# IDC_EXT_Connectors.net
KiCad netlist of a schematic drawn in Altium Designer
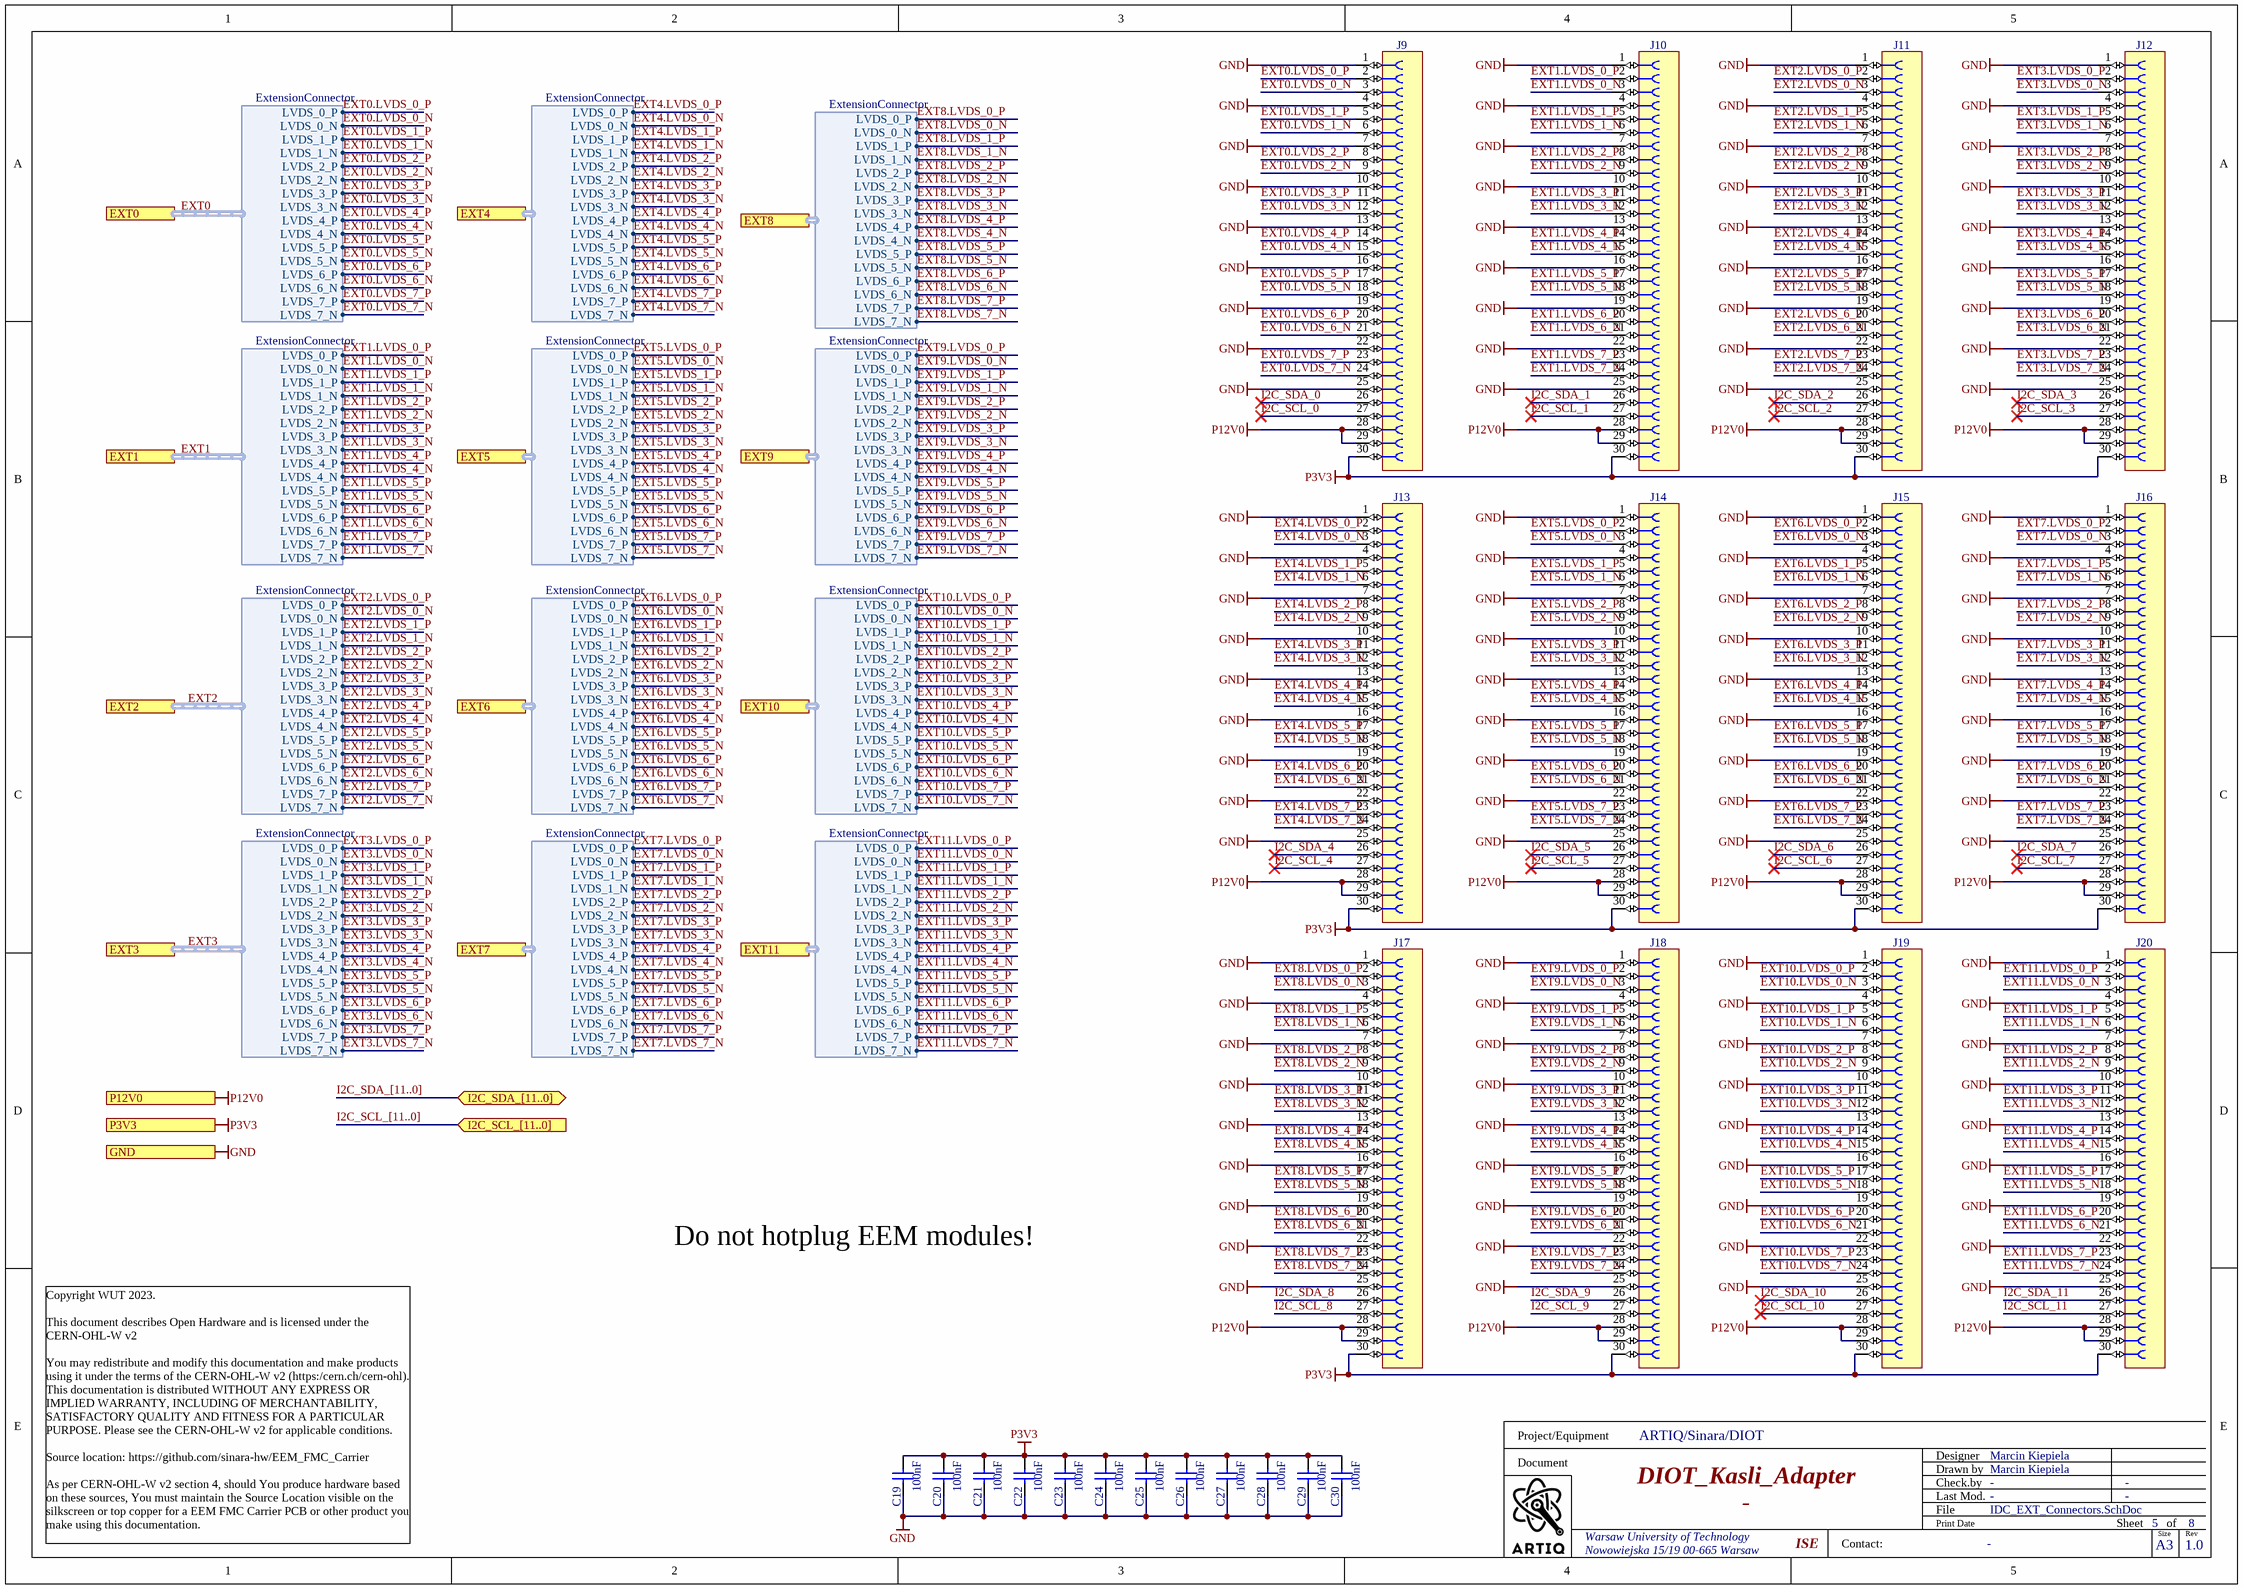
[diagram p0: IDC_EXT_Connectors.SchDoc]

(export (version "E")
  (design (tool "Eeschema 10.0.6"))
  (components
    (comp (ref "C19")
      (value "100nF")
      (footprint "CAPC0603X33N")
      (description "Non-polarised capacitor")
      (fields (field (name "PART NUMBER") "CC0201_100NF_6.3V_10%_X5R") (field (name "VOLTAGE") "6.3V"))
      (libsource (lib "Capacitors") (part "Capacitor - non polarized"))
    )
    (comp (ref "C20")
      (value "100nF")
      (footprint "CAPC0603X33N")
      (description "Non-polarised capacitor")
      (fields (field (name "PART NUMBER") "CC0201_100NF_6.3V_10%_X5R") (field (name "VOLTAGE") "6.3V"))
      (libsource (lib "Capacitors") (part "Capacitor - non polarized"))
    )
    (comp (ref "C21")
      (value "100nF")
      (footprint "CAPC0603X33N")
      (description "Non-polarised capacitor")
      (fields (field (name "PART NUMBER") "CC0201_100NF_6.3V_10%_X5R") (field (name "VOLTAGE") "6.3V"))
      (libsource (lib "Capacitors") (part "Capacitor - non polarized"))
    )
    (comp (ref "C22")
      (value "100nF")
      (footprint "CAPC0603X33N")
      (description "Non-polarised capacitor")
      (fields (field (name "PART NUMBER") "CC0201_100NF_6.3V_10%_X5R") (field (name "VOLTAGE") "6.3V"))
      (libsource (lib "Capacitors") (part "Capacitor - non polarized"))
    )
    (comp (ref "C23")
      (value "100nF")
      (footprint "CAPC0603X33N")
      (description "Non-polarised capacitor")
      (fields (field (name "PART NUMBER") "CC0201_100NF_6.3V_10%_X5R") (field (name "VOLTAGE") "6.3V"))
      (libsource (lib "Capacitors") (part "Capacitor - non polarized"))
    )
    (comp (ref "C24")
      (value "100nF")
      (footprint "CAPC0603X33N")
      (description "Non-polarised capacitor")
      (fields (field (name "PART NUMBER") "CC0201_100NF_6.3V_10%_X5R") (field (name "VOLTAGE") "6.3V"))
      (libsource (lib "Capacitors") (part "Capacitor - non polarized"))
    )
    (comp (ref "C25")
      (value "100nF")
      (footprint "CAPC0603X33N")
      (description "Non-polarised capacitor")
      (fields (field (name "PART NUMBER") "CC0201_100NF_6.3V_10%_X5R") (field (name "VOLTAGE") "6.3V"))
      (libsource (lib "Capacitors") (part "Capacitor - non polarized"))
    )
    (comp (ref "C26")
      (value "100nF")
      (footprint "CAPC0603X33N")
      (description "Non-polarised capacitor")
      (fields (field (name "PART NUMBER") "CC0201_100NF_6.3V_10%_X5R") (field (name "VOLTAGE") "6.3V"))
      (libsource (lib "Capacitors") (part "Capacitor - non polarized"))
    )
    (comp (ref "C27")
      (value "100nF")
      (footprint "CAPC0603X33N")
      (description "Non-polarised capacitor")
      (fields (field (name "PART NUMBER") "CC0201_100NF_6.3V_10%_X5R") (field (name "VOLTAGE") "6.3V"))
      (libsource (lib "Capacitors") (part "Capacitor - non polarized"))
    )
    (comp (ref "C28")
      (value "100nF")
      (footprint "CAPC0603X33N")
      (description "Non-polarised capacitor")
      (fields (field (name "PART NUMBER") "CC0201_100NF_6.3V_10%_X5R") (field (name "VOLTAGE") "6.3V"))
      (libsource (lib "Capacitors") (part "Capacitor - non polarized"))
    )
    (comp (ref "C29")
      (value "100nF")
      (footprint "CAPC0603X33N")
      (description "Non-polarised capacitor")
      (fields (field (name "PART NUMBER") "CC0201_100NF_6.3V_10%_X5R") (field (name "VOLTAGE") "6.3V"))
      (libsource (lib "Capacitors") (part "Capacitor - non polarized"))
    )
    (comp (ref "C30")
      (value "100nF")
      (footprint "CAPC0603X33N")
      (description "Non-polarised capacitor")
      (fields (field (name "PART NUMBER") "CC0201_100NF_6.3V_10%_X5R") (field (name "VOLTAGE") "6.3V"))
      (libsource (lib "Capacitors") (part "Capacitor - non polarized"))
    )
    (comp (ref "J9")
      (value "~")
      (footprint "SAMTEC_ESW-115-44-L-D")
      (description "Elevated Socket Strip, 0.100\" Pitch (2.54mm) Through Hole Gold, 30 pos, duble row")
      (fields (field (name "PART NUMBER") "ESW-115-44-L-D") (field (name "MANUFACTURER") "Samtec"))
      (libsource (lib "MKI_library") (part "CernLib Connector 30 Female"))
    )
    (comp (ref "J10")
      (value "~")
      (footprint "SAMTEC_ESW-115-44-L-D")
      (description "Elevated Socket Strip, 0.100\" Pitch (2.54mm) Through Hole Gold, 30 pos, duble row")
      (fields (field (name "PART NUMBER") "ESW-115-44-L-D") (field (name "MANUFACTURER") "Samtec"))
      (libsource (lib "MKI_library") (part "CernLib Connector 30 Female"))
    )
    (comp (ref "J11")
      (value "~")
      (footprint "SAMTEC_ESW-115-44-L-D")
      (description "Elevated Socket Strip, 0.100\" Pitch (2.54mm) Through Hole Gold, 30 pos, duble row")
      (fields (field (name "PART NUMBER") "ESW-115-44-L-D") (field (name "MANUFACTURER") "Samtec"))
      (libsource (lib "MKI_library") (part "CernLib Connector 30 Female"))
    )
    (comp (ref "J12")
      (value "~")
      (footprint "SAMTEC_ESW-115-44-L-D")
      (description "Elevated Socket Strip, 0.100\" Pitch (2.54mm) Through Hole Gold, 30 pos, duble row")
      (fields (field (name "PART NUMBER") "ESW-115-44-L-D") (field (name "MANUFACTURER") "Samtec"))
      (libsource (lib "MKI_library") (part "CernLib Connector 30 Female"))
    )
    (comp (ref "J13")
      (value "~")
      (footprint "SAMTEC_ESW-115-44-L-D")
      (description "Elevated Socket Strip, 0.100\" Pitch (2.54mm) Through Hole Gold, 30 pos, duble row")
      (fields (field (name "PART NUMBER") "ESW-115-44-L-D") (field (name "MANUFACTURER") "Samtec"))
      (libsource (lib "MKI_library") (part "CernLib Connector 30 Female"))
    )
    (comp (ref "J14")
      (value "~")
      (footprint "SAMTEC_ESW-115-44-L-D")
      (description "Elevated Socket Strip, 0.100\" Pitch (2.54mm) Through Hole Gold, 30 pos, duble row")
      (fields (field (name "PART NUMBER") "ESW-115-44-L-D") (field (name "MANUFACTURER") "Samtec"))
      (libsource (lib "MKI_library") (part "CernLib Connector 30 Female"))
    )
    (comp (ref "J15")
      (value "~")
      (footprint "SAMTEC_ESW-115-44-L-D")
      (description "Elevated Socket Strip, 0.100\" Pitch (2.54mm) Through Hole Gold, 30 pos, duble row")
      (fields (field (name "PART NUMBER") "ESW-115-44-L-D") (field (name "MANUFACTURER") "Samtec"))
      (libsource (lib "MKI_library") (part "CernLib Connector 30 Female"))
    )
    (comp (ref "J16")
      (value "~")
      (footprint "SAMTEC_ESW-115-44-L-D")
      (description "Elevated Socket Strip, 0.100\" Pitch (2.54mm) Through Hole Gold, 30 pos, duble row")
      (fields (field (name "PART NUMBER") "ESW-115-44-L-D") (field (name "MANUFACTURER") "Samtec"))
      (libsource (lib "MKI_library") (part "CernLib Connector 30 Female"))
    )
    (comp (ref "J17")
      (value "~")
      (footprint "SAMTEC_ESW-115-44-L-D")
      (description "Elevated Socket Strip, 0.100\" Pitch (2.54mm) Through Hole Gold, 30 pos, duble row")
      (fields (field (name "PART NUMBER") "ESW-115-44-L-D") (field (name "MANUFACTURER") "Samtec"))
      (libsource (lib "MKI_library") (part "CernLib Connector 30 Female"))
    )
    (comp (ref "J18")
      (value "~")
      (footprint "SAMTEC_ESW-115-44-L-D")
      (description "Elevated Socket Strip, 0.100\" Pitch (2.54mm) Through Hole Gold, 30 pos, duble row")
      (fields (field (name "PART NUMBER") "ESW-115-44-L-D") (field (name "MANUFACTURER") "Samtec"))
      (libsource (lib "MKI_library") (part "CernLib Connector 30 Female"))
    )
    (comp (ref "J19")
      (value "~")
      (footprint "SAMTEC_ESW-115-44-L-D")
      (description "Elevated Socket Strip, 0.100\" Pitch (2.54mm) Through Hole Gold, 30 pos, duble row")
      (fields (field (name "PART NUMBER") "ESW-115-44-L-D") (field (name "MANUFACTURER") "Samtec"))
      (libsource (lib "MKI_library") (part "CernLib Connector 30 Female"))
    )
    (comp (ref "J20")
      (value "~")
      (footprint "SAMTEC_ESW-115-44-L-D")
      (description "Elevated Socket Strip, 0.100\" Pitch (2.54mm) Through Hole Gold, 30 pos, duble row")
      (fields (field (name "PART NUMBER") "ESW-115-44-L-D") (field (name "MANUFACTURER") "Samtec"))
      (libsource (lib "MKI_library") (part "CernLib Connector 30 Female"))
    )
  )
  (nets
    (net (code "6") (name "/EXT0.LVDS_0_N") (class "Default")
      (node (ref "J9") (pin "3") (pinfunction "3_3") (pintype "bidirectional"))
    )
    (net (code "7") (name "/EXT0.LVDS_0_P") (class "Default")
      (node (ref "J9") (pin "2") (pinfunction "2_2") (pintype "bidirectional"))
    )
    (net (code "8") (name "/EXT0.LVDS_1_N") (class "Default")
      (node (ref "J9") (pin "6") (pinfunction "6_6") (pintype "bidirectional"))
    )
    (net (code "9") (name "/EXT0.LVDS_1_P") (class "Default")
      (node (ref "J9") (pin "5") (pinfunction "5_5") (pintype "bidirectional"))
    )
    (net (code "10") (name "/EXT0.LVDS_2_N") (class "Default")
      (node (ref "J9") (pin "9") (pinfunction "9_9") (pintype "bidirectional"))
    )
    (net (code "11") (name "/EXT0.LVDS_2_P") (class "Default")
      (node (ref "J9") (pin "8") (pinfunction "8_8") (pintype "bidirectional"))
    )
    (net (code "12") (name "/EXT0.LVDS_3_N") (class "Default")
      (node (ref "J9") (pin "12") (pinfunction "12_12") (pintype "bidirectional"))
    )
    (net (code "13") (name "/EXT0.LVDS_3_P") (class "Default")
      (node (ref "J9") (pin "11") (pinfunction "11_11") (pintype "bidirectional"))
    )
    (net (code "14") (name "/EXT0.LVDS_4_N") (class "Default")
      (node (ref "J9") (pin "15") (pinfunction "15_15") (pintype "bidirectional"))
    )
    (net (code "15") (name "/EXT0.LVDS_4_P") (class "Default")
      (node (ref "J9") (pin "14") (pinfunction "14_14") (pintype "bidirectional"))
    )
    (net (code "16") (name "/EXT0.LVDS_5_N") (class "Default")
      (node (ref "J9") (pin "18") (pinfunction "18_18") (pintype "bidirectional"))
    )
    (net (code "17") (name "/EXT0.LVDS_5_P") (class "Default")
      (node (ref "J9") (pin "17") (pinfunction "17_17") (pintype "bidirectional"))
    )
    (net (code "18") (name "/EXT0.LVDS_6_N") (class "Default")
      (node (ref "J9") (pin "21") (pinfunction "21_21") (pintype "bidirectional"))
    )
    (net (code "19") (name "/EXT0.LVDS_6_P") (class "Default")
      (node (ref "J9") (pin "20") (pinfunction "20_20") (pintype "bidirectional"))
    )
    (net (code "20") (name "/EXT0.LVDS_7_N") (class "Default")
      (node (ref "J9") (pin "24") (pinfunction "24_24") (pintype "bidirectional"))
    )
    (net (code "21") (name "/EXT0.LVDS_7_P") (class "Default")
      (node (ref "J9") (pin "23") (pinfunction "23_23") (pintype "bidirectional"))
    )
    (net (code "23") (name "/EXT1.LVDS_0_N") (class "Default")
      (node (ref "J10") (pin "3") (pinfunction "3_3") (pintype "bidirectional"))
    )
    (net (code "24") (name "/EXT1.LVDS_0_P") (class "Default")
      (node (ref "J10") (pin "2") (pinfunction "2_2") (pintype "bidirectional"))
    )
    (net (code "25") (name "/EXT1.LVDS_1_N") (class "Default")
      (node (ref "J10") (pin "6") (pinfunction "6_6") (pintype "bidirectional"))
    )
    (net (code "26") (name "/EXT1.LVDS_1_P") (class "Default")
      (node (ref "J10") (pin "5") (pinfunction "5_5") (pintype "bidirectional"))
    )
    (net (code "27") (name "/EXT1.LVDS_2_N") (class "Default")
      (node (ref "J10") (pin "9") (pinfunction "9_9") (pintype "bidirectional"))
    )
    (net (code "28") (name "/EXT1.LVDS_2_P") (class "Default")
      (node (ref "J10") (pin "8") (pinfunction "8_8") (pintype "bidirectional"))
    )
    (net (code "29") (name "/EXT1.LVDS_3_N") (class "Default")
      (node (ref "J10") (pin "12") (pinfunction "12_12") (pintype "bidirectional"))
    )
    (net (code "30") (name "/EXT1.LVDS_3_P") (class "Default")
      (node (ref "J10") (pin "11") (pinfunction "11_11") (pintype "bidirectional"))
    )
    (net (code "31") (name "/EXT1.LVDS_4_N") (class "Default")
      (node (ref "J10") (pin "15") (pinfunction "15_15") (pintype "bidirectional"))
    )
    (net (code "32") (name "/EXT1.LVDS_4_P") (class "Default")
      (node (ref "J10") (pin "14") (pinfunction "14_14") (pintype "bidirectional"))
    )
    (net (code "33") (name "/EXT1.LVDS_5_N") (class "Default")
      (node (ref "J10") (pin "18") (pinfunction "18_18") (pintype "bidirectional"))
    )
    (net (code "34") (name "/EXT1.LVDS_5_P") (class "Default")
      (node (ref "J10") (pin "17") (pinfunction "17_17") (pintype "bidirectional"))
    )
    (net (code "35") (name "/EXT1.LVDS_6_N") (class "Default")
      (node (ref "J10") (pin "21") (pinfunction "21_21") (pintype "bidirectional"))
    )
    (net (code "36") (name "/EXT1.LVDS_6_P") (class "Default")
      (node (ref "J10") (pin "20") (pinfunction "20_20") (pintype "bidirectional"))
    )
    (net (code "37") (name "/EXT1.LVDS_7_N") (class "Default")
      (node (ref "J10") (pin "24") (pinfunction "24_24") (pintype "bidirectional"))
    )
    (net (code "38") (name "/EXT1.LVDS_7_P") (class "Default")
      (node (ref "J10") (pin "23") (pinfunction "23_23") (pintype "bidirectional"))
    )
    (net (code "40") (name "/EXT2.LVDS_0_N") (class "Default")
      (node (ref "J11") (pin "3") (pinfunction "3_3") (pintype "bidirectional"))
    )
    (net (code "41") (name "/EXT2.LVDS_0_P") (class "Default")
      (node (ref "J11") (pin "2") (pinfunction "2_2") (pintype "bidirectional"))
    )
    (net (code "42") (name "/EXT2.LVDS_1_N") (class "Default")
      (node (ref "J11") (pin "6") (pinfunction "6_6") (pintype "bidirectional"))
    )
    (net (code "43") (name "/EXT2.LVDS_1_P") (class "Default")
      (node (ref "J11") (pin "5") (pinfunction "5_5") (pintype "bidirectional"))
    )
    (net (code "44") (name "/EXT2.LVDS_2_N") (class "Default")
      (node (ref "J11") (pin "9") (pinfunction "9_9") (pintype "bidirectional"))
    )
    (net (code "45") (name "/EXT2.LVDS_2_P") (class "Default")
      (node (ref "J11") (pin "8") (pinfunction "8_8") (pintype "bidirectional"))
    )
    (net (code "46") (name "/EXT2.LVDS_3_N") (class "Default")
      (node (ref "J11") (pin "12") (pinfunction "12_12") (pintype "bidirectional"))
    )
    (net (code "47") (name "/EXT2.LVDS_3_P") (class "Default")
      (node (ref "J11") (pin "11") (pinfunction "11_11") (pintype "bidirectional"))
    )
    (net (code "48") (name "/EXT2.LVDS_4_N") (class "Default")
      (node (ref "J11") (pin "15") (pinfunction "15_15") (pintype "bidirectional"))
    )
    (net (code "49") (name "/EXT2.LVDS_4_P") (class "Default")
      (node (ref "J11") (pin "14") (pinfunction "14_14") (pintype "bidirectional"))
    )
    (net (code "50") (name "/EXT2.LVDS_5_N") (class "Default")
      (node (ref "J11") (pin "18") (pinfunction "18_18") (pintype "bidirectional"))
    )
    (net (code "51") (name "/EXT2.LVDS_5_P") (class "Default")
      (node (ref "J11") (pin "17") (pinfunction "17_17") (pintype "bidirectional"))
    )
    (net (code "52") (name "/EXT2.LVDS_6_N") (class "Default")
      (node (ref "J11") (pin "21") (pinfunction "21_21") (pintype "bidirectional"))
    )
    (net (code "53") (name "/EXT2.LVDS_6_P") (class "Default")
      (node (ref "J11") (pin "20") (pinfunction "20_20") (pintype "bidirectional"))
    )
    (net (code "54") (name "/EXT2.LVDS_7_N") (class "Default")
      (node (ref "J11") (pin "24") (pinfunction "24_24") (pintype "bidirectional"))
    )
    (net (code "55") (name "/EXT2.LVDS_7_P") (class "Default")
      (node (ref "J11") (pin "23") (pinfunction "23_23") (pintype "bidirectional"))
    )
    (net (code "57") (name "/EXT3.LVDS_0_N") (class "Default")
      (node (ref "J12") (pin "3") (pinfunction "3_3") (pintype "bidirectional"))
    )
    (net (code "58") (name "/EXT3.LVDS_0_P") (class "Default")
      (node (ref "J12") (pin "2") (pinfunction "2_2") (pintype "bidirectional"))
    )
    (net (code "59") (name "/EXT3.LVDS_1_N") (class "Default")
      (node (ref "J12") (pin "6") (pinfunction "6_6") (pintype "bidirectional"))
    )
    (net (code "60") (name "/EXT3.LVDS_1_P") (class "Default")
      (node (ref "J12") (pin "5") (pinfunction "5_5") (pintype "bidirectional"))
    )
    (net (code "61") (name "/EXT3.LVDS_2_N") (class "Default")
      (node (ref "J12") (pin "9") (pinfunction "9_9") (pintype "bidirectional"))
    )
    (net (code "62") (name "/EXT3.LVDS_2_P") (class "Default")
      (node (ref "J12") (pin "8") (pinfunction "8_8") (pintype "bidirectional"))
    )
    (net (code "63") (name "/EXT3.LVDS_3_N") (class "Default")
      (node (ref "J12") (pin "12") (pinfunction "12_12") (pintype "bidirectional"))
    )
    (net (code "64") (name "/EXT3.LVDS_3_P") (class "Default")
      (node (ref "J12") (pin "11") (pinfunction "11_11") (pintype "bidirectional"))
    )
    (net (code "65") (name "/EXT3.LVDS_4_N") (class "Default")
      (node (ref "J12") (pin "15") (pinfunction "15_15") (pintype "bidirectional"))
    )
    (net (code "66") (name "/EXT3.LVDS_4_P") (class "Default")
      (node (ref "J12") (pin "14") (pinfunction "14_14") (pintype "bidirectional"))
    )
    (net (code "67") (name "/EXT3.LVDS_5_N") (class "Default")
      (node (ref "J12") (pin "18") (pinfunction "18_18") (pintype "bidirectional"))
    )
    (net (code "68") (name "/EXT3.LVDS_5_P") (class "Default")
      (node (ref "J12") (pin "17") (pinfunction "17_17") (pintype "bidirectional"))
    )
    (net (code "69") (name "/EXT3.LVDS_6_N") (class "Default")
      (node (ref "J12") (pin "21") (pinfunction "21_21") (pintype "bidirectional"))
    )
    (net (code "70") (name "/EXT3.LVDS_6_P") (class "Default")
      (node (ref "J12") (pin "20") (pinfunction "20_20") (pintype "bidirectional"))
    )
    (net (code "71") (name "/EXT3.LVDS_7_N") (class "Default")
      (node (ref "J12") (pin "24") (pinfunction "24_24") (pintype "bidirectional"))
    )
    (net (code "72") (name "/EXT3.LVDS_7_P") (class "Default")
      (node (ref "J12") (pin "23") (pinfunction "23_23") (pintype "bidirectional"))
    )
    (net (code "74") (name "/EXT4.LVDS_0_N") (class "Default")
      (node (ref "J13") (pin "3") (pinfunction "3_3") (pintype "bidirectional"))
    )
    (net (code "75") (name "/EXT4.LVDS_0_P") (class "Default")
      (node (ref "J13") (pin "2") (pinfunction "2_2") (pintype "bidirectional"))
    )
    (net (code "76") (name "/EXT4.LVDS_1_N") (class "Default")
      (node (ref "J13") (pin "6") (pinfunction "6_6") (pintype "bidirectional"))
    )
    (net (code "77") (name "/EXT4.LVDS_1_P") (class "Default")
      (node (ref "J13") (pin "5") (pinfunction "5_5") (pintype "bidirectional"))
    )
    (net (code "78") (name "/EXT4.LVDS_2_N") (class "Default")
      (node (ref "J13") (pin "9") (pinfunction "9_9") (pintype "bidirectional"))
    )
    (net (code "79") (name "/EXT4.LVDS_2_P") (class "Default")
      (node (ref "J13") (pin "8") (pinfunction "8_8") (pintype "bidirectional"))
    )
    (net (code "80") (name "/EXT4.LVDS_3_N") (class "Default")
      (node (ref "J13") (pin "12") (pinfunction "12_12") (pintype "bidirectional"))
    )
    (net (code "81") (name "/EXT4.LVDS_3_P") (class "Default")
      (node (ref "J13") (pin "11") (pinfunction "11_11") (pintype "bidirectional"))
    )
    (net (code "82") (name "/EXT4.LVDS_4_N") (class "Default")
      (node (ref "J13") (pin "15") (pinfunction "15_15") (pintype "bidirectional"))
    )
    (net (code "83") (name "/EXT4.LVDS_4_P") (class "Default")
      (node (ref "J13") (pin "14") (pinfunction "14_14") (pintype "bidirectional"))
    )
    (net (code "84") (name "/EXT4.LVDS_5_N") (class "Default")
      (node (ref "J13") (pin "18") (pinfunction "18_18") (pintype "bidirectional"))
    )
    (net (code "85") (name "/EXT4.LVDS_5_P") (class "Default")
      (node (ref "J13") (pin "17") (pinfunction "17_17") (pintype "bidirectional"))
    )
    (net (code "86") (name "/EXT4.LVDS_6_N") (class "Default")
      (node (ref "J13") (pin "21") (pinfunction "21_21") (pintype "bidirectional"))
    )
    (net (code "87") (name "/EXT4.LVDS_6_P") (class "Default")
      (node (ref "J13") (pin "20") (pinfunction "20_20") (pintype "bidirectional"))
    )
    (net (code "88") (name "/EXT4.LVDS_7_N") (class "Default")
      (node (ref "J13") (pin "24") (pinfunction "24_24") (pintype "bidirectional"))
    )
    (net (code "89") (name "/EXT4.LVDS_7_P") (class "Default")
      (node (ref "J13") (pin "23") (pinfunction "23_23") (pintype "bidirectional"))
    )
    (net (code "90") (name "/EXT5.LVDS_0_N") (class "Default")
      (node (ref "J14") (pin "3") (pinfunction "3_3") (pintype "bidirectional"))
    )
    (net (code "91") (name "/EXT5.LVDS_0_P") (class "Default")
      (node (ref "J14") (pin "2") (pinfunction "2_2") (pintype "bidirectional"))
    )
    (net (code "92") (name "/EXT5.LVDS_1_N") (class "Default")
      (node (ref "J14") (pin "6") (pinfunction "6_6") (pintype "bidirectional"))
    )
    (net (code "93") (name "/EXT5.LVDS_1_P") (class "Default")
      (node (ref "J14") (pin "5") (pinfunction "5_5") (pintype "bidirectional"))
    )
    (net (code "94") (name "/EXT5.LVDS_2_N") (class "Default")
      (node (ref "J14") (pin "9") (pinfunction "9_9") (pintype "bidirectional"))
    )
    (net (code "95") (name "/EXT5.LVDS_2_P") (class "Default")
      (node (ref "J14") (pin "8") (pinfunction "8_8") (pintype "bidirectional"))
    )
    (net (code "96") (name "/EXT5.LVDS_3_N") (class "Default")
      (node (ref "J14") (pin "12") (pinfunction "12_12") (pintype "bidirectional"))
    )
    (net (code "97") (name "/EXT5.LVDS_3_P") (class "Default")
      (node (ref "J14") (pin "11") (pinfunction "11_11") (pintype "bidirectional"))
    )
    (net (code "98") (name "/EXT5.LVDS_4_N") (class "Default")
      (node (ref "J14") (pin "15") (pinfunction "15_15") (pintype "bidirectional"))
    )
    (net (code "99") (name "/EXT5.LVDS_4_P") (class "Default")
      (node (ref "J14") (pin "14") (pinfunction "14_14") (pintype "bidirectional"))
    )
    (net (code "100") (name "/EXT5.LVDS_5_N") (class "Default")
      (node (ref "J14") (pin "18") (pinfunction "18_18") (pintype "bidirectional"))
    )
    (net (code "101") (name "/EXT5.LVDS_5_P") (class "Default")
      (node (ref "J14") (pin "17") (pinfunction "17_17") (pintype "bidirectional"))
    )
    (net (code "102") (name "/EXT5.LVDS_6_N") (class "Default")
      (node (ref "J14") (pin "21") (pinfunction "21_21") (pintype "bidirectional"))
    )
    (net (code "103") (name "/EXT5.LVDS_6_P") (class "Default")
      (node (ref "J14") (pin "20") (pinfunction "20_20") (pintype "bidirectional"))
    )
    (net (code "104") (name "/EXT5.LVDS_7_N") (class "Default")
      (node (ref "J14") (pin "24") (pinfunction "24_24") (pintype "bidirectional"))
    )
    (net (code "105") (name "/EXT5.LVDS_7_P") (class "Default")
      (node (ref "J14") (pin "23") (pinfunction "23_23") (pintype "bidirectional"))
    )
    (net (code "106") (name "/EXT6.LVDS_0_N") (class "Default")
      (node (ref "J15") (pin "3") (pinfunction "3_3") (pintype "bidirectional"))
    )
    (net (code "107") (name "/EXT6.LVDS_0_P") (class "Default")
      (node (ref "J15") (pin "2") (pinfunction "2_2") (pintype "bidirectional"))
    )
    (net (code "108") (name "/EXT6.LVDS_1_N") (class "Default")
      (node (ref "J15") (pin "6") (pinfunction "6_6") (pintype "bidirectional"))
    )
    (net (code "109") (name "/EXT6.LVDS_1_P") (class "Default")
      (node (ref "J15") (pin "5") (pinfunction "5_5") (pintype "bidirectional"))
    )
    (net (code "110") (name "/EXT6.LVDS_2_N") (class "Default")
      (node (ref "J15") (pin "9") (pinfunction "9_9") (pintype "bidirectional"))
    )
    (net (code "111") (name "/EXT6.LVDS_2_P") (class "Default")
      (node (ref "J15") (pin "8") (pinfunction "8_8") (pintype "bidirectional"))
    )
    (net (code "112") (name "/EXT6.LVDS_3_N") (class "Default")
      (node (ref "J15") (pin "12") (pinfunction "12_12") (pintype "bidirectional"))
    )
    (net (code "113") (name "/EXT6.LVDS_3_P") (class "Default")
      (node (ref "J15") (pin "11") (pinfunction "11_11") (pintype "bidirectional"))
    )
    (net (code "114") (name "/EXT6.LVDS_4_N") (class "Default")
      (node (ref "J15") (pin "15") (pinfunction "15_15") (pintype "bidirectional"))
    )
    (net (code "115") (name "/EXT6.LVDS_4_P") (class "Default")
      (node (ref "J15") (pin "14") (pinfunction "14_14") (pintype "bidirectional"))
    )
    (net (code "116") (name "/EXT6.LVDS_5_N") (class "Default")
      (node (ref "J15") (pin "18") (pinfunction "18_18") (pintype "bidirectional"))
    )
    (net (code "117") (name "/EXT6.LVDS_5_P") (class "Default")
      (node (ref "J15") (pin "17") (pinfunction "17_17") (pintype "bidirectional"))
    )
    (net (code "118") (name "/EXT6.LVDS_6_N") (class "Default")
      (node (ref "J15") (pin "21") (pinfunction "21_21") (pintype "bidirectional"))
    )
    (net (code "119") (name "/EXT6.LVDS_6_P") (class "Default")
      (node (ref "J15") (pin "20") (pinfunction "20_20") (pintype "bidirectional"))
    )
    (net (code "120") (name "/EXT6.LVDS_7_N") (class "Default")
      (node (ref "J15") (pin "24") (pinfunction "24_24") (pintype "bidirectional"))
    )
    (net (code "121") (name "/EXT6.LVDS_7_P") (class "Default")
      (node (ref "J15") (pin "23") (pinfunction "23_23") (pintype "bidirectional"))
    )
    (net (code "122") (name "/EXT7.LVDS_0_N") (class "Default")
      (node (ref "J16") (pin "3") (pinfunction "3_3") (pintype "bidirectional"))
    )
    (net (code "123") (name "/EXT7.LVDS_0_P") (class "Default")
      (node (ref "J16") (pin "2") (pinfunction "2_2") (pintype "bidirectional"))
    )
    (net (code "124") (name "/EXT7.LVDS_1_N") (class "Default")
      (node (ref "J16") (pin "6") (pinfunction "6_6") (pintype "bidirectional"))
    )
    (net (code "125") (name "/EXT7.LVDS_1_P") (class "Default")
      (node (ref "J16") (pin "5") (pinfunction "5_5") (pintype "bidirectional"))
    )
    (net (code "126") (name "/EXT7.LVDS_2_N") (class "Default")
      (node (ref "J16") (pin "9") (pinfunction "9_9") (pintype "bidirectional"))
    )
    (net (code "127") (name "/EXT7.LVDS_2_P") (class "Default")
      (node (ref "J16") (pin "8") (pinfunction "8_8") (pintype "bidirectional"))
    )
    (net (code "128") (name "/EXT7.LVDS_3_N") (class "Default")
      (node (ref "J16") (pin "12") (pinfunction "12_12") (pintype "bidirectional"))
    )
    (net (code "129") (name "/EXT7.LVDS_3_P") (class "Default")
      (node (ref "J16") (pin "11") (pinfunction "11_11") (pintype "bidirectional"))
    )
    (net (code "130") (name "/EXT7.LVDS_4_N") (class "Default")
      (node (ref "J16") (pin "15") (pinfunction "15_15") (pintype "bidirectional"))
    )
    (net (code "131") (name "/EXT7.LVDS_4_P") (class "Default")
      (node (ref "J16") (pin "14") (pinfunction "14_14") (pintype "bidirectional"))
    )
    (net (code "132") (name "/EXT7.LVDS_5_N") (class "Default")
      (node (ref "J16") (pin "18") (pinfunction "18_18") (pintype "bidirectional"))
    )
    (net (code "133") (name "/EXT7.LVDS_5_P") (class "Default")
      (node (ref "J16") (pin "17") (pinfunction "17_17") (pintype "bidirectional"))
    )
    (net (code "134") (name "/EXT7.LVDS_6_N") (class "Default")
      (node (ref "J16") (pin "21") (pinfunction "21_21") (pintype "bidirectional"))
    )
    (net (code "135") (name "/EXT7.LVDS_6_P") (class "Default")
      (node (ref "J16") (pin "20") (pinfunction "20_20") (pintype "bidirectional"))
    )
    (net (code "136") (name "/EXT7.LVDS_7_N") (class "Default")
      (node (ref "J16") (pin "24") (pinfunction "24_24") (pintype "bidirectional"))
    )
    (net (code "137") (name "/EXT7.LVDS_7_P") (class "Default")
      (node (ref "J16") (pin "23") (pinfunction "23_23") (pintype "bidirectional"))
    )
    (net (code "138") (name "/EXT8.LVDS_0_N") (class "Default")
      (node (ref "J17") (pin "3") (pinfunction "3_3") (pintype "bidirectional"))
    )
    (net (code "139") (name "/EXT8.LVDS_0_P") (class "Default")
      (node (ref "J17") (pin "2") (pinfunction "2_2") (pintype "bidirectional"))
    )
    (net (code "140") (name "/EXT8.LVDS_1_N") (class "Default")
      (node (ref "J17") (pin "6") (pinfunction "6_6") (pintype "bidirectional"))
    )
    (net (code "141") (name "/EXT8.LVDS_1_P") (class "Default")
      (node (ref "J17") (pin "5") (pinfunction "5_5") (pintype "bidirectional"))
    )
    (net (code "142") (name "/EXT8.LVDS_2_N") (class "Default")
      (node (ref "J17") (pin "9") (pinfunction "9_9") (pintype "bidirectional"))
    )
    (net (code "143") (name "/EXT8.LVDS_2_P") (class "Default")
      (node (ref "J17") (pin "8") (pinfunction "8_8") (pintype "bidirectional"))
    )
    (net (code "144") (name "/EXT8.LVDS_3_N") (class "Default")
      (node (ref "J17") (pin "12") (pinfunction "12_12") (pintype "bidirectional"))
    )
    (net (code "145") (name "/EXT8.LVDS_3_P") (class "Default")
      (node (ref "J17") (pin "11") (pinfunction "11_11") (pintype "bidirectional"))
    )
    (net (code "146") (name "/EXT8.LVDS_4_N") (class "Default")
      (node (ref "J17") (pin "15") (pinfunction "15_15") (pintype "bidirectional"))
    )
    (net (code "147") (name "/EXT8.LVDS_4_P") (class "Default")
      (node (ref "J17") (pin "14") (pinfunction "14_14") (pintype "bidirectional"))
    )
    (net (code "148") (name "/EXT8.LVDS_5_N") (class "Default")
      (node (ref "J17") (pin "18") (pinfunction "18_18") (pintype "bidirectional"))
    )
    (net (code "149") (name "/EXT8.LVDS_5_P") (class "Default")
      (node (ref "J17") (pin "17") (pinfunction "17_17") (pintype "bidirectional"))
    )
    (net (code "150") (name "/EXT8.LVDS_6_N") (class "Default")
      (node (ref "J17") (pin "21") (pinfunction "21_21") (pintype "bidirectional"))
    )
    (net (code "151") (name "/EXT8.LVDS_6_P") (class "Default")
      (node (ref "J17") (pin "20") (pinfunction "20_20") (pintype "bidirectional"))
    )
    (net (code "152") (name "/EXT8.LVDS_7_N") (class "Default")
      (node (ref "J17") (pin "24") (pinfunction "24_24") (pintype "bidirectional"))
    )
    (net (code "153") (name "/EXT8.LVDS_7_P") (class "Default")
      (node (ref "J17") (pin "23") (pinfunction "23_23") (pintype "bidirectional"))
    )
    (net (code "154") (name "/EXT9.LVDS_0_N") (class "Default")
      (node (ref "J18") (pin "3") (pinfunction "3_3") (pintype "bidirectional"))
    )
    (net (code "155") (name "/EXT9.LVDS_0_P") (class "Default")
      (node (ref "J18") (pin "2") (pinfunction "2_2") (pintype "bidirectional"))
    )
    (net (code "156") (name "/EXT9.LVDS_1_N") (class "Default")
      (node (ref "J18") (pin "6") (pinfunction "6_6") (pintype "bidirectional"))
    )
    (net (code "157") (name "/EXT9.LVDS_1_P") (class "Default")
      (node (ref "J18") (pin "5") (pinfunction "5_5") (pintype "bidirectional"))
    )
    (net (code "158") (name "/EXT9.LVDS_2_N") (class "Default")
      (node (ref "J18") (pin "9") (pinfunction "9_9") (pintype "bidirectional"))
    )
    (net (code "159") (name "/EXT9.LVDS_2_P") (class "Default")
      (node (ref "J18") (pin "8") (pinfunction "8_8") (pintype "bidirectional"))
    )
    (net (code "160") (name "/EXT9.LVDS_3_N") (class "Default")
      (node (ref "J18") (pin "12") (pinfunction "12_12") (pintype "bidirectional"))
    )
    (net (code "161") (name "/EXT9.LVDS_3_P") (class "Default")
      (node (ref "J18") (pin "11") (pinfunction "11_11") (pintype "bidirectional"))
    )
    (net (code "162") (name "/EXT9.LVDS_4_N") (class "Default")
      (node (ref "J18") (pin "15") (pinfunction "15_15") (pintype "bidirectional"))
    )
    (net (code "163") (name "/EXT9.LVDS_4_P") (class "Default")
      (node (ref "J18") (pin "14") (pinfunction "14_14") (pintype "bidirectional"))
    )
    (net (code "164") (name "/EXT9.LVDS_5_N") (class "Default")
      (node (ref "J18") (pin "18") (pinfunction "18_18") (pintype "bidirectional"))
    )
    (net (code "165") (name "/EXT9.LVDS_5_P") (class "Default")
      (node (ref "J18") (pin "17") (pinfunction "17_17") (pintype "bidirectional"))
    )
    (net (code "166") (name "/EXT9.LVDS_6_N") (class "Default")
      (node (ref "J18") (pin "21") (pinfunction "21_21") (pintype "bidirectional"))
    )
    (net (code "167") (name "/EXT9.LVDS_6_P") (class "Default")
      (node (ref "J18") (pin "20") (pinfunction "20_20") (pintype "bidirectional"))
    )
    (net (code "168") (name "/EXT9.LVDS_7_N") (class "Default")
      (node (ref "J18") (pin "24") (pinfunction "24_24") (pintype "bidirectional"))
    )
    (net (code "169") (name "/EXT9.LVDS_7_P") (class "Default")
      (node (ref "J18") (pin "23") (pinfunction "23_23") (pintype "bidirectional"))
    )
    (net (code "170") (name "/EXT10.LVDS_0_N") (class "Default")
      (node (ref "J19") (pin "3") (pinfunction "3_3") (pintype "bidirectional"))
    )
    (net (code "171") (name "/EXT10.LVDS_0_P") (class "Default")
      (node (ref "J19") (pin "2") (pinfunction "2_2") (pintype "bidirectional"))
    )
    (net (code "172") (name "/EXT10.LVDS_1_N") (class "Default")
      (node (ref "J19") (pin "6") (pinfunction "6_6") (pintype "bidirectional"))
    )
    (net (code "173") (name "/EXT10.LVDS_1_P") (class "Default")
      (node (ref "J19") (pin "5") (pinfunction "5_5") (pintype "bidirectional"))
    )
    (net (code "174") (name "/EXT10.LVDS_2_N") (class "Default")
      (node (ref "J19") (pin "9") (pinfunction "9_9") (pintype "bidirectional"))
    )
    (net (code "175") (name "/EXT10.LVDS_2_P") (class "Default")
      (node (ref "J19") (pin "8") (pinfunction "8_8") (pintype "bidirectional"))
    )
    (net (code "176") (name "/EXT10.LVDS_3_N") (class "Default")
      (node (ref "J19") (pin "12") (pinfunction "12_12") (pintype "bidirectional"))
    )
    (net (code "177") (name "/EXT10.LVDS_3_P") (class "Default")
      (node (ref "J19") (pin "11") (pinfunction "11_11") (pintype "bidirectional"))
    )
    (net (code "178") (name "/EXT10.LVDS_4_N") (class "Default")
      (node (ref "J19") (pin "15") (pinfunction "15_15") (pintype "bidirectional"))
    )
    (net (code "179") (name "/EXT10.LVDS_4_P") (class "Default")
      (node (ref "J19") (pin "14") (pinfunction "14_14") (pintype "bidirectional"))
    )
    (net (code "180") (name "/EXT10.LVDS_5_N") (class "Default")
      (node (ref "J19") (pin "18") (pinfunction "18_18") (pintype "bidirectional"))
    )
    (net (code "181") (name "/EXT10.LVDS_5_P") (class "Default")
      (node (ref "J19") (pin "17") (pinfunction "17_17") (pintype "bidirectional"))
    )
    (net (code "182") (name "/EXT10.LVDS_6_N") (class "Default")
      (node (ref "J19") (pin "21") (pinfunction "21_21") (pintype "bidirectional"))
    )
    (net (code "183") (name "/EXT10.LVDS_6_P") (class "Default")
      (node (ref "J19") (pin "20") (pinfunction "20_20") (pintype "bidirectional"))
    )
    (net (code "184") (name "/EXT10.LVDS_7_N") (class "Default")
      (node (ref "J19") (pin "24") (pinfunction "24_24") (pintype "bidirectional"))
    )
    (net (code "185") (name "/EXT10.LVDS_7_P") (class "Default")
      (node (ref "J19") (pin "23") (pinfunction "23_23") (pintype "bidirectional"))
    )
    (net (code "186") (name "/EXT11.LVDS_0_N") (class "Default")
      (node (ref "J20") (pin "3") (pinfunction "3_3") (pintype "bidirectional"))
    )
    (net (code "187") (name "/EXT11.LVDS_0_P") (class "Default")
      (node (ref "J20") (pin "2") (pinfunction "2_2") (pintype "bidirectional"))
    )
    (net (code "188") (name "/EXT11.LVDS_1_N") (class "Default")
      (node (ref "J20") (pin "6") (pinfunction "6_6") (pintype "bidirectional"))
    )
    (net (code "189") (name "/EXT11.LVDS_1_P") (class "Default")
      (node (ref "J20") (pin "5") (pinfunction "5_5") (pintype "bidirectional"))
    )
    (net (code "190") (name "/EXT11.LVDS_2_N") (class "Default")
      (node (ref "J20") (pin "9") (pinfunction "9_9") (pintype "bidirectional"))
    )
    (net (code "191") (name "/EXT11.LVDS_2_P") (class "Default")
      (node (ref "J20") (pin "8") (pinfunction "8_8") (pintype "bidirectional"))
    )
    (net (code "192") (name "/EXT11.LVDS_3_N") (class "Default")
      (node (ref "J20") (pin "12") (pinfunction "12_12") (pintype "bidirectional"))
    )
    (net (code "193") (name "/EXT11.LVDS_3_P") (class "Default")
      (node (ref "J20") (pin "11") (pinfunction "11_11") (pintype "bidirectional"))
    )
    (net (code "194") (name "/EXT11.LVDS_4_N") (class "Default")
      (node (ref "J20") (pin "15") (pinfunction "15_15") (pintype "bidirectional"))
    )
    (net (code "195") (name "/EXT11.LVDS_4_P") (class "Default")
      (node (ref "J20") (pin "14") (pinfunction "14_14") (pintype "bidirectional"))
    )
    (net (code "196") (name "/EXT11.LVDS_5_N") (class "Default")
      (node (ref "J20") (pin "18") (pinfunction "18_18") (pintype "bidirectional"))
    )
    (net (code "197") (name "/EXT11.LVDS_5_P") (class "Default")
      (node (ref "J20") (pin "17") (pinfunction "17_17") (pintype "bidirectional"))
    )
    (net (code "198") (name "/EXT11.LVDS_6_N") (class "Default")
      (node (ref "J20") (pin "21") (pinfunction "21_21") (pintype "bidirectional"))
    )
    (net (code "199") (name "/EXT11.LVDS_6_P") (class "Default")
      (node (ref "J20") (pin "20") (pinfunction "20_20") (pintype "bidirectional"))
    )
    (net (code "200") (name "/EXT11.LVDS_7_N") (class "Default")
      (node (ref "J20") (pin "24") (pinfunction "24_24") (pintype "bidirectional"))
    )
    (net (code "201") (name "/EXT11.LVDS_7_P") (class "Default")
      (node (ref "J20") (pin "23") (pinfunction "23_23") (pintype "bidirectional"))
    )
    (net (code "202") (name "/I2C_SCL_0") (class "Default")
      (node (ref "J9") (pin "27") (pinfunction "27_27") (pintype "bidirectional+no_connect"))
    )
    (net (code "203") (name "/I2C_SCL_1") (class "Default")
      (node (ref "J10") (pin "27") (pinfunction "27_27") (pintype "bidirectional+no_connect"))
    )
    (net (code "204") (name "/I2C_SCL_2") (class "Default")
      (node (ref "J11") (pin "27") (pinfunction "27_27") (pintype "bidirectional+no_connect"))
    )
    (net (code "205") (name "/I2C_SCL_3") (class "Default")
      (node (ref "J12") (pin "27") (pinfunction "27_27") (pintype "bidirectional+no_connect"))
    )
    (net (code "206") (name "/I2C_SCL_4") (class "Default")
      (node (ref "J13") (pin "27") (pinfunction "27_27") (pintype "bidirectional+no_connect"))
    )
    (net (code "207") (name "/I2C_SCL_5") (class "Default")
      (node (ref "J14") (pin "27") (pinfunction "27_27") (pintype "bidirectional+no_connect"))
    )
    (net (code "208") (name "/I2C_SCL_6") (class "Default")
      (node (ref "J15") (pin "27") (pinfunction "27_27") (pintype "bidirectional+no_connect"))
    )
    (net (code "209") (name "/I2C_SCL_7") (class "Default")
      (node (ref "J16") (pin "27") (pinfunction "27_27") (pintype "bidirectional+no_connect"))
    )
    (net (code "210") (name "/I2C_SCL_8") (class "Default")
      (node (ref "J17") (pin "27") (pinfunction "27_27") (pintype "bidirectional"))
    )
    (net (code "211") (name "/I2C_SCL_9") (class "Default")
      (node (ref "J18") (pin "27") (pinfunction "27_27") (pintype "bidirectional"))
    )
    (net (code "212") (name "/I2C_SCL_10") (class "Default")
      (node (ref "J19") (pin "27") (pinfunction "27_27") (pintype "bidirectional+no_connect"))
    )
    (net (code "213") (name "/I2C_SCL_11") (class "Default")
      (node (ref "J20") (pin "27") (pinfunction "27_27") (pintype "bidirectional"))
    )
    (net (code "215") (name "/I2C_SDA_0") (class "Default")
      (node (ref "J9") (pin "26") (pinfunction "26_26") (pintype "bidirectional+no_connect"))
    )
    (net (code "216") (name "/I2C_SDA_1") (class "Default")
      (node (ref "J10") (pin "26") (pinfunction "26_26") (pintype "bidirectional+no_connect"))
    )
    (net (code "217") (name "/I2C_SDA_2") (class "Default")
      (node (ref "J11") (pin "26") (pinfunction "26_26") (pintype "bidirectional+no_connect"))
    )
    (net (code "218") (name "/I2C_SDA_3") (class "Default")
      (node (ref "J12") (pin "26") (pinfunction "26_26") (pintype "bidirectional+no_connect"))
    )
    (net (code "219") (name "/I2C_SDA_4") (class "Default")
      (node (ref "J13") (pin "26") (pinfunction "26_26") (pintype "bidirectional+no_connect"))
    )
    (net (code "220") (name "/I2C_SDA_5") (class "Default")
      (node (ref "J14") (pin "26") (pinfunction "26_26") (pintype "bidirectional+no_connect"))
    )
    (net (code "221") (name "/I2C_SDA_6") (class "Default")
      (node (ref "J15") (pin "26") (pinfunction "26_26") (pintype "bidirectional+no_connect"))
    )
    (net (code "222") (name "/I2C_SDA_7") (class "Default")
      (node (ref "J16") (pin "26") (pinfunction "26_26") (pintype "bidirectional+no_connect"))
    )
    (net (code "223") (name "/I2C_SDA_8") (class "Default")
      (node (ref "J17") (pin "26") (pinfunction "26_26") (pintype "bidirectional"))
    )
    (net (code "224") (name "/I2C_SDA_9") (class "Default")
      (node (ref "J18") (pin "26") (pinfunction "26_26") (pintype "bidirectional"))
    )
    (net (code "225") (name "/I2C_SDA_10") (class "Default")
      (node (ref "J19") (pin "26") (pinfunction "26_26") (pintype "bidirectional+no_connect"))
    )
    (net (code "226") (name "/I2C_SDA_11") (class "Default")
      (node (ref "J20") (pin "26") (pinfunction "26_26") (pintype "bidirectional"))
    )
    (net (code "229") (name "GND") (class "Default")
      (node (ref "C19") (pin "1") (pinfunction "1_1") (pintype "passive"))
      (node (ref "C20") (pin "1") (pinfunction "1_1") (pintype "passive"))
      (node (ref "C21") (pin "1") (pinfunction "1_1") (pintype "passive"))
      (node (ref "C22") (pin "1") (pinfunction "1_1") (pintype "passive"))
      (node (ref "C23") (pin "1") (pinfunction "1_1") (pintype "passive"))
      (node (ref "C24") (pin "1") (pinfunction "1_1") (pintype "passive"))
      (node (ref "C25") (pin "1") (pinfunction "1_1") (pintype "passive"))
      (node (ref "C26") (pin "1") (pinfunction "1_1") (pintype "passive"))
      (node (ref "C27") (pin "1") (pinfunction "1_1") (pintype "passive"))
      (node (ref "C28") (pin "1") (pinfunction "1_1") (pintype "passive"))
      (node (ref "C29") (pin "1") (pinfunction "1_1") (pintype "passive"))
      (node (ref "C30") (pin "1") (pinfunction "1_1") (pintype "passive"))
      (node (ref "J10") (pin "1") (pinfunction "1_1") (pintype "bidirectional"))
      (node (ref "J10") (pin "10") (pinfunction "10_10") (pintype "bidirectional"))
      (node (ref "J10") (pin "13") (pinfunction "13_13") (pintype "bidirectional"))
      (node (ref "J10") (pin "16") (pinfunction "16_16") (pintype "bidirectional"))
      (node (ref "J10") (pin "19") (pinfunction "19_19") (pintype "bidirectional"))
      (node (ref "J10") (pin "22") (pinfunction "22_22") (pintype "bidirectional"))
      (node (ref "J10") (pin "25") (pinfunction "25_25") (pintype "bidirectional"))
      (node (ref "J10") (pin "4") (pinfunction "4_4") (pintype "bidirectional"))
      (node (ref "J10") (pin "7") (pinfunction "7_7") (pintype "bidirectional"))
      (node (ref "J11") (pin "1") (pinfunction "1_1") (pintype "bidirectional"))
      (node (ref "J11") (pin "10") (pinfunction "10_10") (pintype "bidirectional"))
      (node (ref "J11") (pin "13") (pinfunction "13_13") (pintype "bidirectional"))
      (node (ref "J11") (pin "16") (pinfunction "16_16") (pintype "bidirectional"))
      (node (ref "J11") (pin "19") (pinfunction "19_19") (pintype "bidirectional"))
      (node (ref "J11") (pin "22") (pinfunction "22_22") (pintype "bidirectional"))
      (node (ref "J11") (pin "25") (pinfunction "25_25") (pintype "bidirectional"))
      (node (ref "J11") (pin "4") (pinfunction "4_4") (pintype "bidirectional"))
      (node (ref "J11") (pin "7") (pinfunction "7_7") (pintype "bidirectional"))
      (node (ref "J12") (pin "1") (pinfunction "1_1") (pintype "bidirectional"))
      (node (ref "J12") (pin "10") (pinfunction "10_10") (pintype "bidirectional"))
      (node (ref "J12") (pin "13") (pinfunction "13_13") (pintype "bidirectional"))
      (node (ref "J12") (pin "16") (pinfunction "16_16") (pintype "bidirectional"))
      (node (ref "J12") (pin "19") (pinfunction "19_19") (pintype "bidirectional"))
      (node (ref "J12") (pin "22") (pinfunction "22_22") (pintype "bidirectional"))
      (node (ref "J12") (pin "25") (pinfunction "25_25") (pintype "bidirectional"))
      (node (ref "J12") (pin "4") (pinfunction "4_4") (pintype "bidirectional"))
      (node (ref "J12") (pin "7") (pinfunction "7_7") (pintype "bidirectional"))
      (node (ref "J13") (pin "1") (pinfunction "1_1") (pintype "bidirectional"))
      (node (ref "J13") (pin "10") (pinfunction "10_10") (pintype "bidirectional"))
      (node (ref "J13") (pin "13") (pinfunction "13_13") (pintype "bidirectional"))
      (node (ref "J13") (pin "16") (pinfunction "16_16") (pintype "bidirectional"))
      (node (ref "J13") (pin "19") (pinfunction "19_19") (pintype "bidirectional"))
      (node (ref "J13") (pin "22") (pinfunction "22_22") (pintype "bidirectional"))
      (node (ref "J13") (pin "25") (pinfunction "25_25") (pintype "bidirectional"))
      (node (ref "J13") (pin "4") (pinfunction "4_4") (pintype "bidirectional"))
      (node (ref "J13") (pin "7") (pinfunction "7_7") (pintype "bidirectional"))
      (node (ref "J14") (pin "1") (pinfunction "1_1") (pintype "bidirectional"))
      (node (ref "J14") (pin "10") (pinfunction "10_10") (pintype "bidirectional"))
      (node (ref "J14") (pin "13") (pinfunction "13_13") (pintype "bidirectional"))
      (node (ref "J14") (pin "16") (pinfunction "16_16") (pintype "bidirectional"))
      (node (ref "J14") (pin "19") (pinfunction "19_19") (pintype "bidirectional"))
      (node (ref "J14") (pin "22") (pinfunction "22_22") (pintype "bidirectional"))
      (node (ref "J14") (pin "25") (pinfunction "25_25") (pintype "bidirectional"))
      (node (ref "J14") (pin "4") (pinfunction "4_4") (pintype "bidirectional"))
      (node (ref "J14") (pin "7") (pinfunction "7_7") (pintype "bidirectional"))
      (node (ref "J15") (pin "1") (pinfunction "1_1") (pintype "bidirectional"))
      (node (ref "J15") (pin "10") (pinfunction "10_10") (pintype "bidirectional"))
      (node (ref "J15") (pin "13") (pinfunction "13_13") (pintype "bidirectional"))
      (node (ref "J15") (pin "16") (pinfunction "16_16") (pintype "bidirectional"))
      (node (ref "J15") (pin "19") (pinfunction "19_19") (pintype "bidirectional"))
      (node (ref "J15") (pin "22") (pinfunction "22_22") (pintype "bidirectional"))
      (node (ref "J15") (pin "25") (pinfunction "25_25") (pintype "bidirectional"))
      (node (ref "J15") (pin "4") (pinfunction "4_4") (pintype "bidirectional"))
      (node (ref "J15") (pin "7") (pinfunction "7_7") (pintype "bidirectional"))
      (node (ref "J16") (pin "1") (pinfunction "1_1") (pintype "bidirectional"))
      (node (ref "J16") (pin "10") (pinfunction "10_10") (pintype "bidirectional"))
      (node (ref "J16") (pin "13") (pinfunction "13_13") (pintype "bidirectional"))
      (node (ref "J16") (pin "16") (pinfunction "16_16") (pintype "bidirectional"))
      (node (ref "J16") (pin "19") (pinfunction "19_19") (pintype "bidirectional"))
      (node (ref "J16") (pin "22") (pinfunction "22_22") (pintype "bidirectional"))
      (node (ref "J16") (pin "25") (pinfunction "25_25") (pintype "bidirectional"))
      (node (ref "J16") (pin "4") (pinfunction "4_4") (pintype "bidirectional"))
      (node (ref "J16") (pin "7") (pinfunction "7_7") (pintype "bidirectional"))
      (node (ref "J17") (pin "1") (pinfunction "1_1") (pintype "bidirectional"))
      (node (ref "J17") (pin "10") (pinfunction "10_10") (pintype "bidirectional"))
      (node (ref "J17") (pin "13") (pinfunction "13_13") (pintype "bidirectional"))
      (node (ref "J17") (pin "16") (pinfunction "16_16") (pintype "bidirectional"))
      (node (ref "J17") (pin "19") (pinfunction "19_19") (pintype "bidirectional"))
      (node (ref "J17") (pin "22") (pinfunction "22_22") (pintype "bidirectional"))
      (node (ref "J17") (pin "25") (pinfunction "25_25") (pintype "bidirectional"))
      (node (ref "J17") (pin "4") (pinfunction "4_4") (pintype "bidirectional"))
      (node (ref "J17") (pin "7") (pinfunction "7_7") (pintype "bidirectional"))
      (node (ref "J18") (pin "1") (pinfunction "1_1") (pintype "bidirectional"))
      (node (ref "J18") (pin "10") (pinfunction "10_10") (pintype "bidirectional"))
      (node (ref "J18") (pin "13") (pinfunction "13_13") (pintype "bidirectional"))
      (node (ref "J18") (pin "16") (pinfunction "16_16") (pintype "bidirectional"))
      (node (ref "J18") (pin "19") (pinfunction "19_19") (pintype "bidirectional"))
      (node (ref "J18") (pin "22") (pinfunction "22_22") (pintype "bidirectional"))
      (node (ref "J18") (pin "25") (pinfunction "25_25") (pintype "bidirectional"))
      (node (ref "J18") (pin "4") (pinfunction "4_4") (pintype "bidirectional"))
      (node (ref "J18") (pin "7") (pinfunction "7_7") (pintype "bidirectional"))
      (node (ref "J19") (pin "1") (pinfunction "1_1") (pintype "bidirectional"))
      (node (ref "J19") (pin "10") (pinfunction "10_10") (pintype "bidirectional"))
      (node (ref "J19") (pin "13") (pinfunction "13_13") (pintype "bidirectional"))
      (node (ref "J19") (pin "16") (pinfunction "16_16") (pintype "bidirectional"))
      (node (ref "J19") (pin "19") (pinfunction "19_19") (pintype "bidirectional"))
      (node (ref "J19") (pin "22") (pinfunction "22_22") (pintype "bidirectional"))
      (node (ref "J19") (pin "25") (pinfunction "25_25") (pintype "bidirectional"))
      (node (ref "J19") (pin "4") (pinfunction "4_4") (pintype "bidirectional"))
      (node (ref "J19") (pin "7") (pinfunction "7_7") (pintype "bidirectional"))
      (node (ref "J20") (pin "1") (pinfunction "1_1") (pintype "bidirectional"))
      (node (ref "J20") (pin "10") (pinfunction "10_10") (pintype "bidirectional"))
      (node (ref "J20") (pin "13") (pinfunction "13_13") (pintype "bidirectional"))
      (node (ref "J20") (pin "16") (pinfunction "16_16") (pintype "bidirectional"))
      (node (ref "J20") (pin "19") (pinfunction "19_19") (pintype "bidirectional"))
      (node (ref "J20") (pin "22") (pinfunction "22_22") (pintype "bidirectional"))
      (node (ref "J20") (pin "25") (pinfunction "25_25") (pintype "bidirectional"))
      (node (ref "J20") (pin "4") (pinfunction "4_4") (pintype "bidirectional"))
      (node (ref "J20") (pin "7") (pinfunction "7_7") (pintype "bidirectional"))
      (node (ref "J9") (pin "1") (pinfunction "1_1") (pintype "bidirectional"))
      (node (ref "J9") (pin "10") (pinfunction "10_10") (pintype "bidirectional"))
      (node (ref "J9") (pin "13") (pinfunction "13_13") (pintype "bidirectional"))
      (node (ref "J9") (pin "16") (pinfunction "16_16") (pintype "bidirectional"))
      (node (ref "J9") (pin "19") (pinfunction "19_19") (pintype "bidirectional"))
      (node (ref "J9") (pin "22") (pinfunction "22_22") (pintype "bidirectional"))
      (node (ref "J9") (pin "25") (pinfunction "25_25") (pintype "bidirectional"))
      (node (ref "J9") (pin "4") (pinfunction "4_4") (pintype "bidirectional"))
      (node (ref "J9") (pin "7") (pinfunction "7_7") (pintype "bidirectional"))
    )
    (net (code "230") (name "P3V3") (class "Default")
      (node (ref "C19") (pin "2") (pinfunction "2_2") (pintype "passive"))
      (node (ref "C20") (pin "2") (pinfunction "2_2") (pintype "passive"))
      (node (ref "C21") (pin "2") (pinfunction "2_2") (pintype "passive"))
      (node (ref "C22") (pin "2") (pinfunction "2_2") (pintype "passive"))
      (node (ref "C23") (pin "2") (pinfunction "2_2") (pintype "passive"))
      (node (ref "C24") (pin "2") (pinfunction "2_2") (pintype "passive"))
      (node (ref "C25") (pin "2") (pinfunction "2_2") (pintype "passive"))
      (node (ref "C26") (pin "2") (pinfunction "2_2") (pintype "passive"))
      (node (ref "C27") (pin "2") (pinfunction "2_2") (pintype "passive"))
      (node (ref "C28") (pin "2") (pinfunction "2_2") (pintype "passive"))
      (node (ref "C29") (pin "2") (pinfunction "2_2") (pintype "passive"))
      (node (ref "C30") (pin "2") (pinfunction "2_2") (pintype "passive"))
      (node (ref "J10") (pin "30") (pinfunction "30_30") (pintype "bidirectional"))
      (node (ref "J11") (pin "30") (pinfunction "30_30") (pintype "bidirectional"))
      (node (ref "J12") (pin "30") (pinfunction "30_30") (pintype "bidirectional"))
      (node (ref "J13") (pin "30") (pinfunction "30_30") (pintype "bidirectional"))
      (node (ref "J14") (pin "30") (pinfunction "30_30") (pintype "bidirectional"))
      (node (ref "J15") (pin "30") (pinfunction "30_30") (pintype "bidirectional"))
      (node (ref "J16") (pin "30") (pinfunction "30_30") (pintype "bidirectional"))
      (node (ref "J17") (pin "30") (pinfunction "30_30") (pintype "bidirectional"))
      (node (ref "J18") (pin "30") (pinfunction "30_30") (pintype "bidirectional"))
      (node (ref "J19") (pin "30") (pinfunction "30_30") (pintype "bidirectional"))
      (node (ref "J20") (pin "30") (pinfunction "30_30") (pintype "bidirectional"))
      (node (ref "J9") (pin "30") (pinfunction "30_30") (pintype "bidirectional"))
    )
    (net (code "231") (name "P12V0") (class "Default")
      (node (ref "J10") (pin "28") (pinfunction "28_28") (pintype "bidirectional"))
      (node (ref "J10") (pin "29") (pinfunction "29_29") (pintype "bidirectional"))
      (node (ref "J11") (pin "28") (pinfunction "28_28") (pintype "bidirectional"))
      (node (ref "J11") (pin "29") (pinfunction "29_29") (pintype "bidirectional"))
      (node (ref "J12") (pin "28") (pinfunction "28_28") (pintype "bidirectional"))
      (node (ref "J12") (pin "29") (pinfunction "29_29") (pintype "bidirectional"))
      (node (ref "J13") (pin "28") (pinfunction "28_28") (pintype "bidirectional"))
      (node (ref "J13") (pin "29") (pinfunction "29_29") (pintype "bidirectional"))
      (node (ref "J14") (pin "28") (pinfunction "28_28") (pintype "bidirectional"))
      (node (ref "J14") (pin "29") (pinfunction "29_29") (pintype "bidirectional"))
      (node (ref "J15") (pin "28") (pinfunction "28_28") (pintype "bidirectional"))
      (node (ref "J15") (pin "29") (pinfunction "29_29") (pintype "bidirectional"))
      (node (ref "J16") (pin "28") (pinfunction "28_28") (pintype "bidirectional"))
      (node (ref "J16") (pin "29") (pinfunction "29_29") (pintype "bidirectional"))
      (node (ref "J17") (pin "28") (pinfunction "28_28") (pintype "bidirectional"))
      (node (ref "J17") (pin "29") (pinfunction "29_29") (pintype "bidirectional"))
      (node (ref "J18") (pin "28") (pinfunction "28_28") (pintype "bidirectional"))
      (node (ref "J18") (pin "29") (pinfunction "29_29") (pintype "bidirectional"))
      (node (ref "J19") (pin "28") (pinfunction "28_28") (pintype "bidirectional"))
      (node (ref "J19") (pin "29") (pinfunction "29_29") (pintype "bidirectional"))
      (node (ref "J20") (pin "28") (pinfunction "28_28") (pintype "bidirectional"))
      (node (ref "J20") (pin "29") (pinfunction "29_29") (pintype "bidirectional"))
      (node (ref "J9") (pin "28") (pinfunction "28_28") (pintype "bidirectional"))
      (node (ref "J9") (pin "29") (pinfunction "29_29") (pintype "bidirectional"))
    )
  )
)
